# ARDBRKOUT1.net
KiCad netlist of a schematic drawn in EAGLE
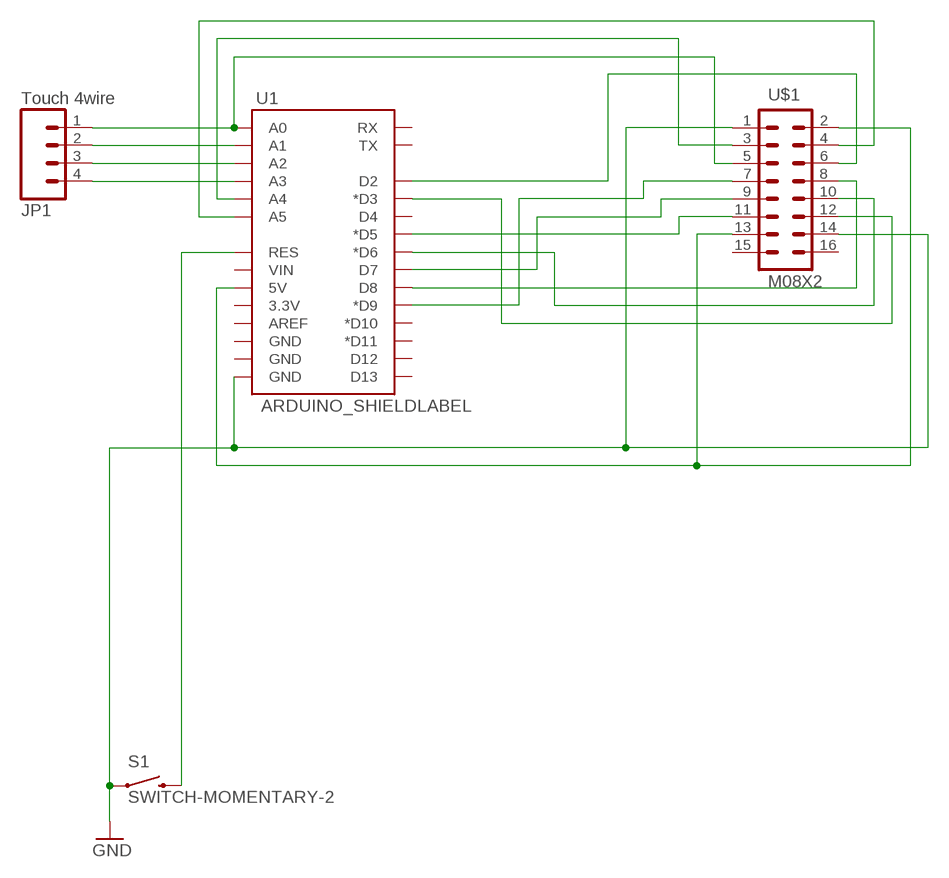
[diagram p0: schematic, sheet 1]

(export (version "E")
  (design (tool "Eeschema 10.0.6"))
  (components
    (comp (ref "JP1")
      (value "Touch 4wire")
      (footprint "eagle-import:1X04")
      (libsource (lib "eagle-import") (part "M04PTH"))
    )
    (comp (ref "S1")
      (value "SWITCH-MOMENTARY-2")
      (footprint "eagle-import:TACTILE_SWITCH_TALL")
      (libsource (lib "eagle-import") (part "SWITCH-MOMENTARY-2"))
    )
    (comp (ref "U$1")
      (value "M08X2")
      (footprint "eagle-import:2X8")
      (libsource (lib "eagle-import") (part "M08X2"))
    )
    (comp (ref "U1")
      (value "ARDUINO_SHIELDLABEL")
      (footprint "eagle-import:DUEMILANOVE_SHIELD")
      (libsource (lib "eagle-import") (part "ARDUINO_SHIELDLABEL"))
    )
  )
  (nets
    (net (code "1") (name "GND") (class "Default")
      (node (ref "S1") (pin "A2") (pinfunction "1_A2") (pintype "passive"))
      (node (ref "U$1") (pin "1") (pinfunction "1_1") (pintype "passive"))
      (node (ref "U$1") (pin "14") (pinfunction "14_14") (pintype "passive"))
      (node (ref "U1") (pin "GND@0") (pinfunction "GND_GND@0") (pintype "bidirectional"))
    )
    (net (code "2") (name "Net-(JP1-Pad1)") (class "Default")
      (node (ref "JP1") (pin "1") (pinfunction "1_1") (pintype "passive"))
      (node (ref "U$1") (pin "5") (pinfunction "5_5") (pintype "passive"))
      (node (ref "U1") (pin "A0") (pinfunction "A0_A0") (pintype "bidirectional"))
    )
    (net (code "3") (name "Net-(JP1-Pad2)") (class "Default")
      (node (ref "JP1") (pin "2") (pinfunction "2_2") (pintype "passive"))
      (node (ref "U1") (pin "A1") (pinfunction "A1_A1") (pintype "bidirectional"))
    )
    (net (code "4") (name "Net-(JP1-Pad3)") (class "Default")
      (node (ref "JP1") (pin "3") (pinfunction "3_3") (pintype "passive"))
      (node (ref "U1") (pin "A2") (pinfunction "A2_A2") (pintype "bidirectional"))
    )
    (net (code "5") (name "Net-(JP1-Pad4)") (class "Default")
      (node (ref "JP1") (pin "4") (pinfunction "4_4") (pintype "passive"))
      (node (ref "U1") (pin "A3") (pinfunction "A3_A3") (pintype "bidirectional"))
    )
    (net (code "6") (name "Net-(S1-2)") (class "Default")
      (node (ref "S1") (pin "B2") (pinfunction "2_B2") (pintype "passive"))
      (node (ref "U1") (pin "RES") (pinfunction "RES_RES") (pintype "bidirectional"))
    )
    (net (code "7") (name "Net-(U$1-Pad3)") (class "Default")
      (node (ref "U$1") (pin "3") (pinfunction "3_3") (pintype "passive"))
      (node (ref "U1") (pin "A4") (pinfunction "A4_A4") (pintype "bidirectional"))
    )
    (net (code "8") (name "Net-(U$1-Pad4)") (class "Default")
      (node (ref "U$1") (pin "4") (pinfunction "4_4") (pintype "passive"))
      (node (ref "U1") (pin "A5") (pinfunction "A5_A5") (pintype "bidirectional"))
    )
    (net (code "9") (name "Net-(U$1-Pad6)") (class "Default")
      (node (ref "U$1") (pin "6") (pinfunction "6_6") (pintype "passive"))
      (node (ref "U1") (pin "D2") (pinfunction "D2_D2") (pintype "bidirectional"))
    )
    (net (code "10") (name "Net-(U$1-Pad8)") (class "Default")
      (node (ref "U$1") (pin "8") (pinfunction "8_8") (pintype "passive"))
      (node (ref "U1") (pin "D8") (pinfunction "D8_D8") (pintype "bidirectional"))
    )
    (net (code "11") (name "Net-(U$1-Pad9)") (class "Default")
      (node (ref "U$1") (pin "9") (pinfunction "9_9") (pintype "passive"))
      (node (ref "U1") (pin "D7") (pinfunction "D7_D7") (pintype "bidirectional"))
    )
    (net (code "12") (name "Net-(U$1-Pad13)") (class "Default")
      (node (ref "U$1") (pin "13") (pinfunction "13_13") (pintype "passive"))
      (node (ref "U$1") (pin "2") (pinfunction "2_2") (pintype "passive"))
      (node (ref "U1") (pin "5V") (pinfunction "5V_5V") (pintype "bidirectional"))
    )
    (net (code "13") (name "Net-(U1-*D3)") (class "Default")
      (node (ref "U$1") (pin "12") (pinfunction "12_12") (pintype "passive"))
      (node (ref "U1") (pin "D3") (pinfunction "*D3_D3") (pintype "bidirectional"))
    )
    (net (code "14") (name "Net-(U1-*D5)") (class "Default")
      (node (ref "U$1") (pin "11") (pinfunction "11_11") (pintype "passive"))
      (node (ref "U1") (pin "D5") (pinfunction "*D5_D5") (pintype "bidirectional"))
    )
    (net (code "15") (name "Net-(U1-*D6)") (class "Default")
      (node (ref "U$1") (pin "10") (pinfunction "10_10") (pintype "passive"))
      (node (ref "U1") (pin "D6") (pinfunction "*D6_D6") (pintype "bidirectional"))
    )
    (net (code "16") (name "Net-(U1-*D9)") (class "Default")
      (node (ref "U$1") (pin "7") (pinfunction "7_7") (pintype "passive"))
      (node (ref "U1") (pin "D9") (pinfunction "*D9_D9") (pintype "bidirectional"))
    )
    (net (code "17") (name "unconnected-(U$1-Pad15)") (class "Default")
      (node (ref "U$1") (pin "15") (pinfunction "15_15") (pintype "passive"))
    )
    (net (code "18") (name "unconnected-(U$1-Pad16)") (class "Default")
      (node (ref "U$1") (pin "16") (pinfunction "16_16") (pintype "passive"))
    )
    (net (code "19") (name "unconnected-(U1-*D10-PadD10)") (class "Default")
      (node (ref "U1") (pin "D10") (pinfunction "*D10_D10") (pintype "bidirectional"))
    )
    (net (code "20") (name "unconnected-(U1-*D11-PadD11)") (class "Default")
      (node (ref "U1") (pin "D11") (pinfunction "*D11_D11") (pintype "bidirectional"))
    )
    (net (code "21") (name "unconnected-(U1-GND-PadGND@1)") (class "Default")
      (node (ref "U1") (pin "GND@1") (pinfunction "GND_GND@1") (pintype "bidirectional"))
    )
    (net (code "22") (name "unconnected-(U1-GND-PadGND@2)") (class "Default")
      (node (ref "U1") (pin "GND@2") (pinfunction "GND_GND@2") (pintype "bidirectional"))
    )
    (net (code "23") (name "unconnected-(U1-Pad3.3V)") (class "Default")
      (node (ref "U1") (pin "3.3V") (pinfunction "3.3V_3.3V") (pintype "bidirectional"))
    )
    (net (code "24") (name "unconnected-(U1-PadAREF)") (class "Default")
      (node (ref "U1") (pin "AREF") (pinfunction "AREF_AREF") (pintype "bidirectional"))
    )
    (net (code "25") (name "unconnected-(U1-PadD4)") (class "Default")
      (node (ref "U1") (pin "D4") (pinfunction "D4_D4") (pintype "bidirectional"))
    )
    (net (code "26") (name "unconnected-(U1-PadD12)") (class "Default")
      (node (ref "U1") (pin "D12") (pinfunction "D12_D12") (pintype "bidirectional"))
    )
    (net (code "27") (name "unconnected-(U1-PadD13)") (class "Default")
      (node (ref "U1") (pin "D13") (pinfunction "D13_D13") (pintype "bidirectional"))
    )
    (net (code "28") (name "unconnected-(U1-PadRX)") (class "Default")
      (node (ref "U1") (pin "RX") (pinfunction "RX_RX") (pintype "bidirectional"))
    )
    (net (code "29") (name "unconnected-(U1-PadTX)") (class "Default")
      (node (ref "U1") (pin "TX") (pinfunction "TX_TX") (pintype "bidirectional"))
    )
    (net (code "30") (name "unconnected-(U1-PadVIN)") (class "Default")
      (node (ref "U1") (pin "VIN") (pinfunction "VIN_VIN") (pintype "bidirectional"))
    )
  )
)
